# MCPICKUP.net
KiCad netlist of a schematic drawn in EasyEDA
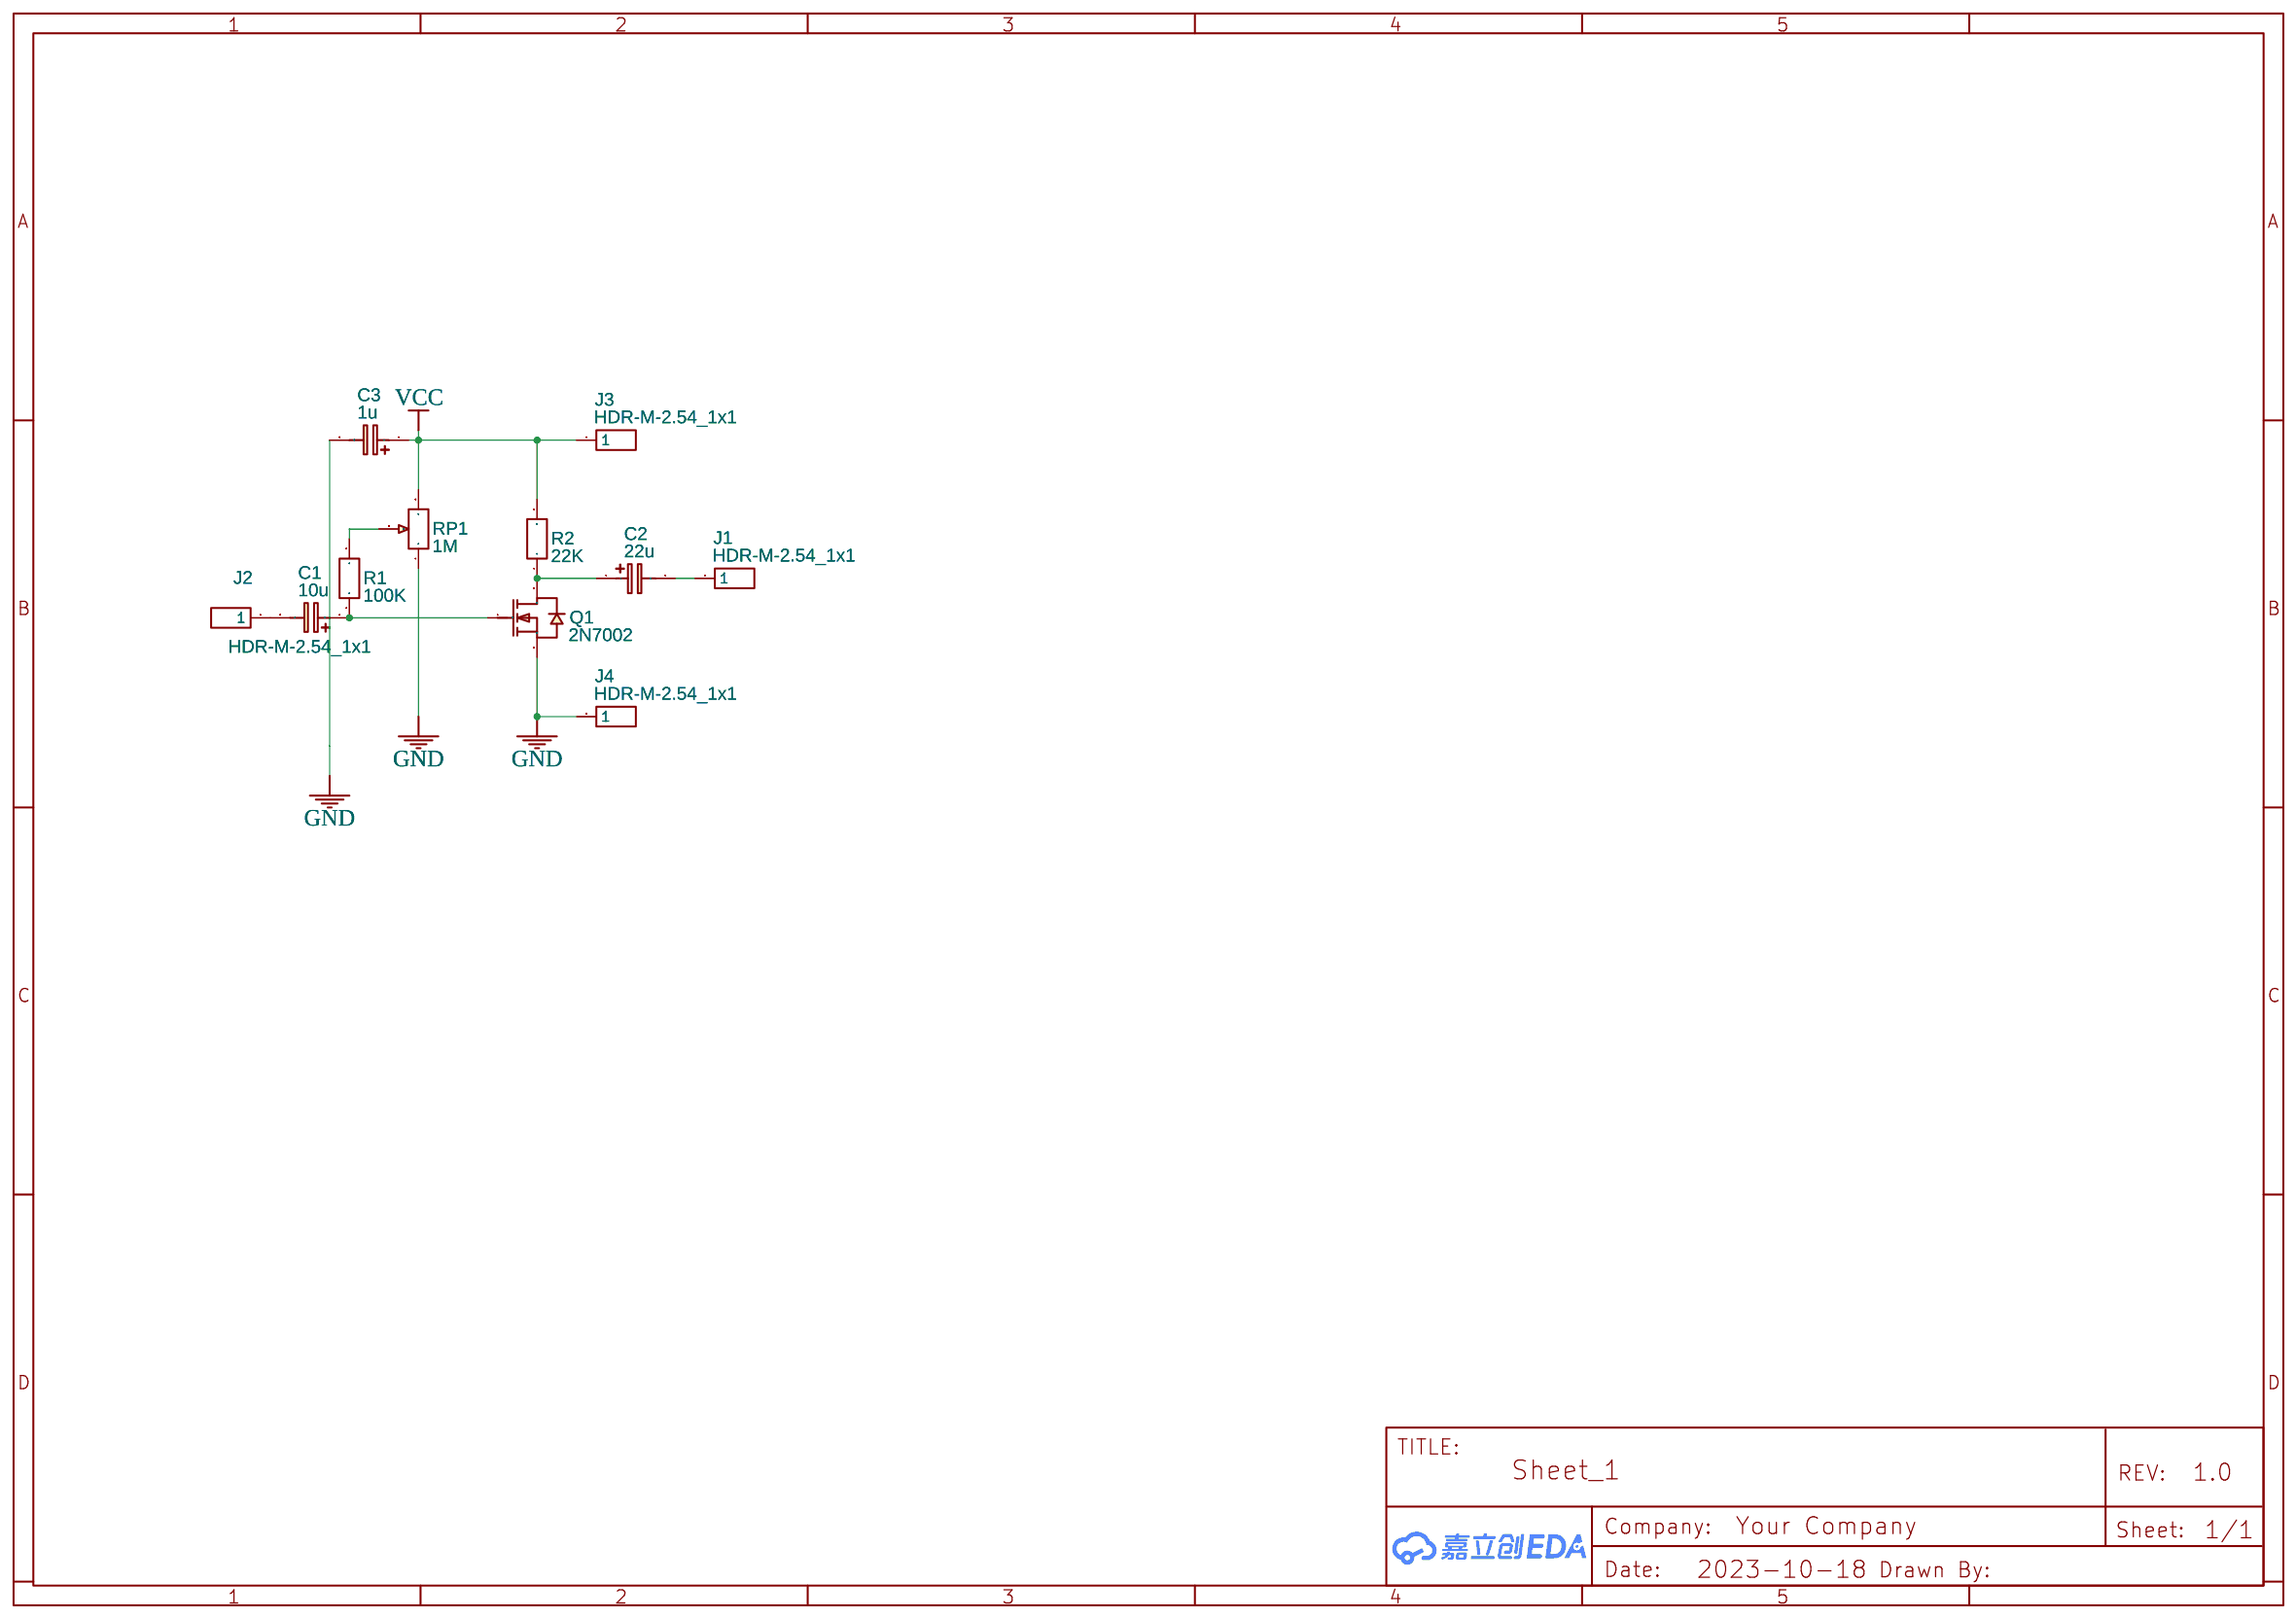
[diagram p0: schematic sheet]

(export (version "E")
  (design (tool "Eeschema 10.0.6"))
  (components
    (comp (ref "C1") (value "10u") (libsource (lib "") (part "C_Tan_SMD_A_EU")))
    (comp (ref "C2") (value "22u") (libsource (lib "") (part "C_Tan_SMD_A_EU_2")))
    (comp (ref "C3") (value "1u") (libsource (lib "") (part "C_Tan_SMD_A_EU_1")))
    (comp (ref "J1")
      (value "HDR-M-2.54_1x1")
      (fields (field (name "BOM_Supplier Part") "C81276"))
      (libsource (lib "") (part "HDR-M-2.54_1x1"))
    )
    (comp (ref "J2")
      (value "HDR-M-2.54_1x1")
      (fields (field (name "BOM_Supplier Part") "C81276"))
      (libsource (lib "") (part "HDR-M-2.54_1x1_1"))
    )
    (comp (ref "J3")
      (value "HDR-M-2.54_1x1")
      (fields (field (name "BOM_Supplier Part") "C81276"))
      (libsource (lib "") (part "HDR-M-2.54_1x1"))
    )
    (comp (ref "J4")
      (value "HDR-M-2.54_1x1")
      (fields (field (name "BOM_Supplier Part") "C81276"))
      (libsource (lib "") (part "HDR-M-2.54_1x1"))
    )
    (comp (ref "Q1")
      (value "2N7002")
      (fields (field (name "BOM_Manufacturer Part") "2N7002,215") (field (name "BOM_Supplier Part") "C65189"))
      (libsource (lib "") (part "2N7002"))
    )
    (comp (ref "R1") (value "100K") (libsource (lib "") (part "R_0603_EU")))
    (comp (ref "R2") (value "22K") (libsource (lib "") (part "R_0603_EU")))
    (comp (ref "RP1") (value "1M") (libsource (lib "") (part "R_3296W_EU")))
  )
  (nets
    (net (code "1") (name "GND") (class "Default")
      (node (ref "C3") (pin "2") (pinfunction "2_2") (pintype "unspecified"))
      (node (ref "J4") (pin "1") (pinfunction "1_1") (pintype "input"))
      (node (ref "Q1") (pin "2") (pinfunction "S_2") (pintype "unspecified"))
      (node (ref "RP1") (pin "1") (pinfunction "1_1") (pintype "input"))
    )
    (net (code "2") (name "Net-(C1-Pad2)") (class "Default")
      (node (ref "C1") (pin "2") (pinfunction "2_2") (pintype "unspecified"))
      (node (ref "J2") (pin "1") (pinfunction "1_1") (pintype "input"))
    )
    (net (code "3") (name "Net-(C2-Pad2)") (class "Default")
      (node (ref "C2") (pin "2") (pinfunction "2_2") (pintype "unspecified"))
      (node (ref "J1") (pin "1") (pinfunction "1_1") (pintype "input"))
    )
    (net (code "4") (name "Net-(Q1-D)") (class "Default")
      (node (ref "C2") (pin "1") (pinfunction "1_1") (pintype "unspecified"))
      (node (ref "Q1") (pin "3") (pinfunction "D_3") (pintype "unspecified"))
      (node (ref "R2") (pin "1") (pinfunction "1_1") (pintype "unspecified"))
    )
    (net (code "5") (name "Net-(Q1-G)") (class "Default")
      (node (ref "C1") (pin "1") (pinfunction "1_1") (pintype "unspecified"))
      (node (ref "Q1") (pin "1") (pinfunction "G_1") (pintype "unspecified"))
      (node (ref "R1") (pin "1") (pinfunction "1_1") (pintype "unspecified"))
    )
    (net (code "6") (name "Net-(R1-Pad2)") (class "Default")
      (node (ref "R1") (pin "2") (pinfunction "2_2") (pintype "unspecified"))
      (node (ref "RP1") (pin "2") (pinfunction "2_2") (pintype "input"))
    )
    (net (code "7") (name "VCC") (class "Default")
      (node (ref "C3") (pin "1") (pinfunction "1_1") (pintype "unspecified"))
      (node (ref "J3") (pin "1") (pinfunction "1_1") (pintype "input"))
      (node (ref "R2") (pin "2") (pinfunction "2_2") (pintype "unspecified"))
      (node (ref "RP1") (pin "3") (pinfunction "3_3") (pintype "input"))
    )
  )
)
